# Main.net
KiCad netlist of a schematic drawn in Altium Designer
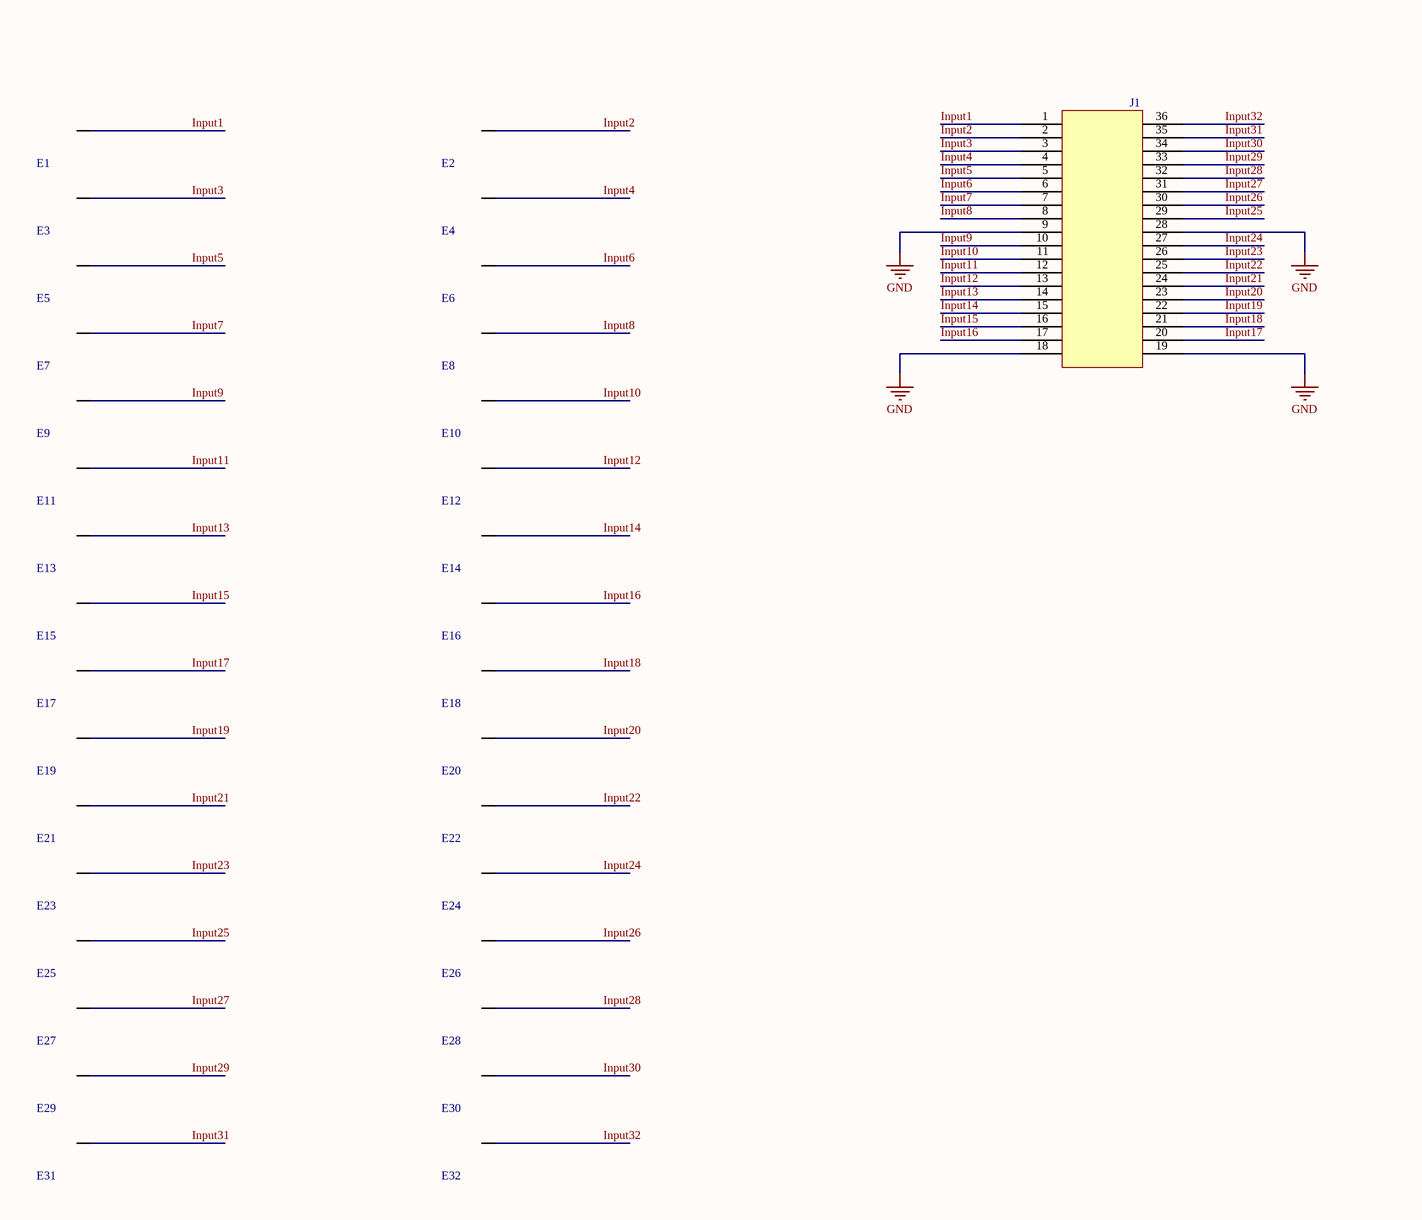
[diagram p0: Main.SchDoc, left]
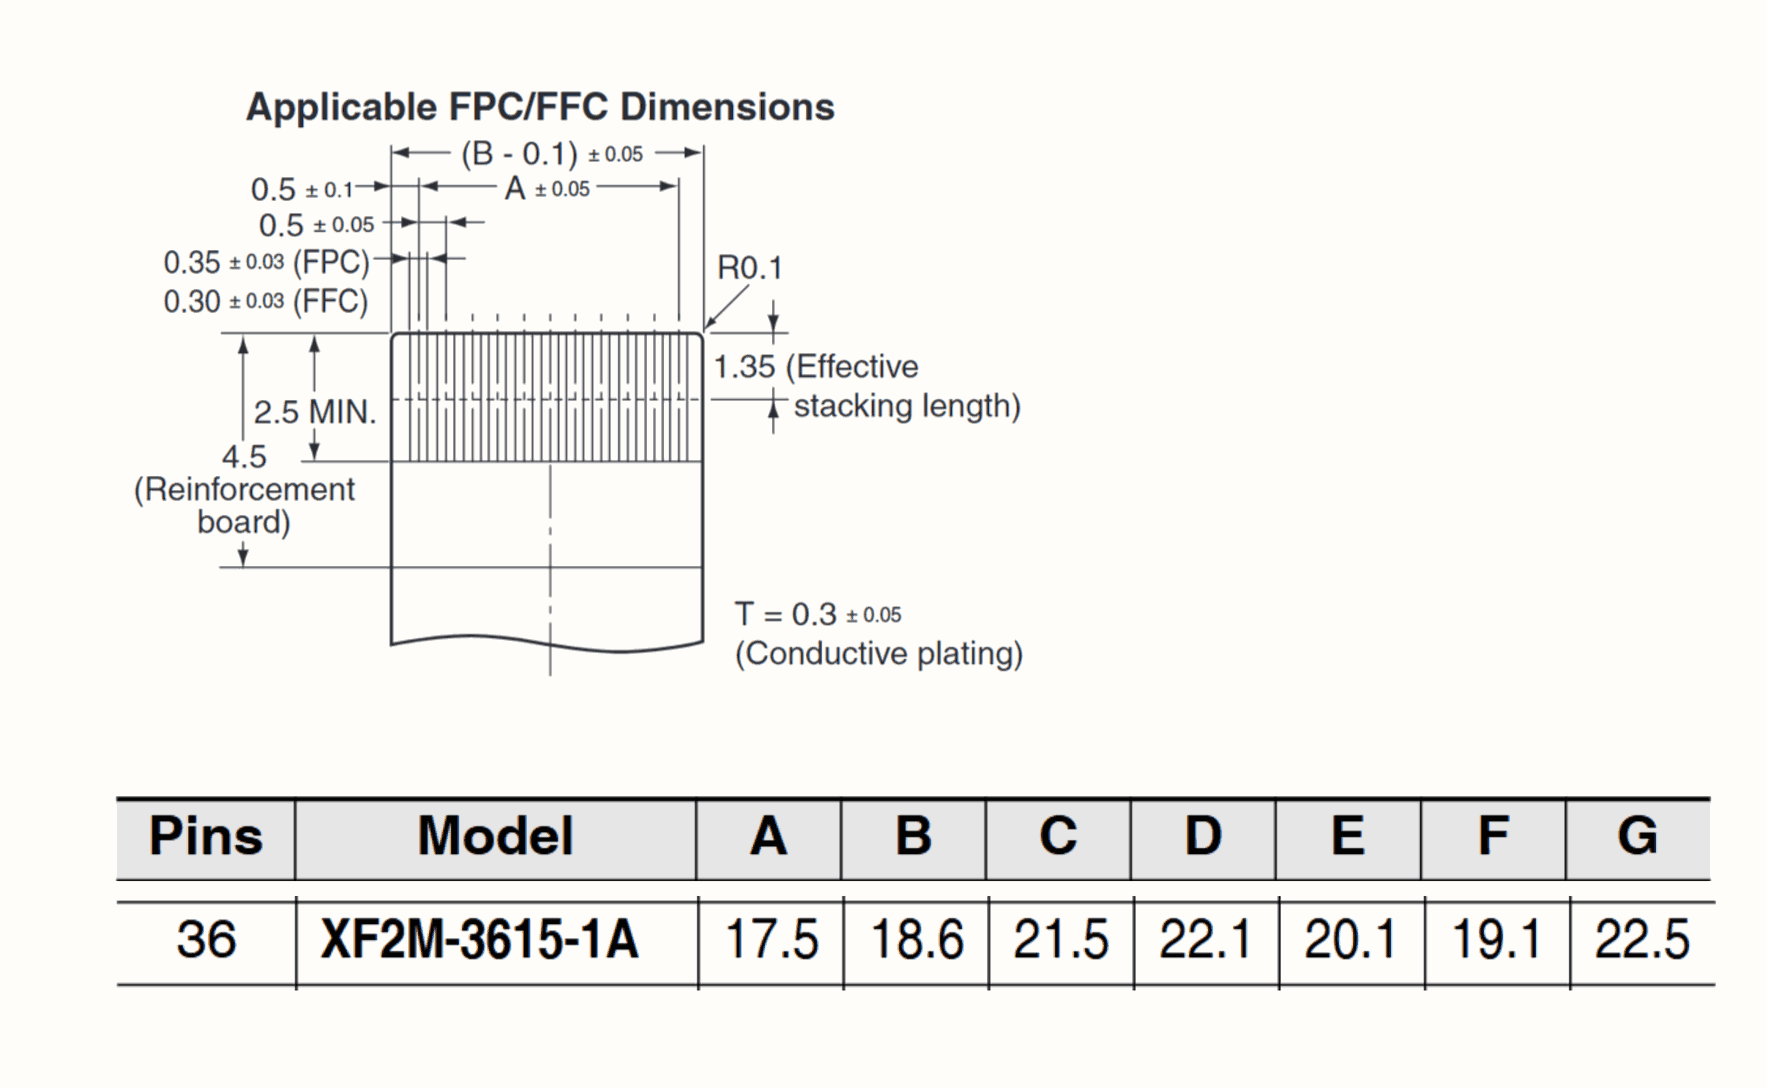
[diagram p1: Main.SchDoc, right]

(export (version "E")
  (design (tool "Eeschema 10.0.6"))
  (components
    (comp (ref "E1")
      (value "2.5 mm")
      (footprint "PCBComponent_1")
      (description "Microneedle electrode - 2.5 mm diameter")
      (libsource (lib "Microneedle_Lib") (part "SENSE_UNEEDLE"))
    )
    (comp (ref "E2")
      (value "2.5 mm")
      (footprint "PCBComponent_1")
      (description "Microneedle electrode - 2.5 mm diameter")
      (libsource (lib "Microneedle_Lib") (part "SENSE_UNEEDLE"))
    )
    (comp (ref "E3")
      (value "2.5 mm")
      (footprint "PCBComponent_1")
      (description "Microneedle electrode - 2.5 mm diameter")
      (libsource (lib "Microneedle_Lib") (part "SENSE_UNEEDLE"))
    )
    (comp (ref "E4")
      (value "2.5 mm")
      (footprint "PCBComponent_1")
      (description "Microneedle electrode - 2.5 mm diameter")
      (libsource (lib "Microneedle_Lib") (part "SENSE_UNEEDLE"))
    )
    (comp (ref "E5")
      (value "2.5 mm")
      (footprint "PCBComponent_1")
      (description "Microneedle electrode - 2.5 mm diameter")
      (libsource (lib "Microneedle_Lib") (part "SENSE_UNEEDLE"))
    )
    (comp (ref "E6")
      (value "2.5 mm")
      (footprint "PCBComponent_1")
      (description "Microneedle electrode - 2.5 mm diameter")
      (libsource (lib "Microneedle_Lib") (part "SENSE_UNEEDLE"))
    )
    (comp (ref "E7")
      (value "2.5 mm")
      (footprint "PCBComponent_1")
      (description "Microneedle electrode - 2.5 mm diameter")
      (libsource (lib "Microneedle_Lib") (part "SENSE_UNEEDLE"))
    )
    (comp (ref "E8")
      (value "2.5 mm")
      (footprint "PCBComponent_1")
      (description "Microneedle electrode - 2.5 mm diameter")
      (libsource (lib "Microneedle_Lib") (part "SENSE_UNEEDLE"))
    )
    (comp (ref "E9")
      (value "2.5 mm")
      (footprint "PCBComponent_1")
      (description "Microneedle electrode - 2.5 mm diameter")
      (libsource (lib "Microneedle_Lib") (part "SENSE_UNEEDLE"))
    )
    (comp (ref "E10")
      (value "2.5 mm")
      (footprint "PCBComponent_1")
      (description "Microneedle electrode - 2.5 mm diameter")
      (libsource (lib "Microneedle_Lib") (part "SENSE_UNEEDLE"))
    )
    (comp (ref "E11")
      (value "2.5 mm")
      (footprint "PCBComponent_1")
      (description "Microneedle electrode - 2.5 mm diameter")
      (libsource (lib "Microneedle_Lib") (part "SENSE_UNEEDLE"))
    )
    (comp (ref "E12")
      (value "2.5 mm")
      (footprint "PCBComponent_1")
      (description "Microneedle electrode - 2.5 mm diameter")
      (libsource (lib "Microneedle_Lib") (part "SENSE_UNEEDLE"))
    )
    (comp (ref "E13")
      (value "2.5 mm")
      (footprint "PCBComponent_1")
      (description "Microneedle electrode - 2.5 mm diameter")
      (libsource (lib "Microneedle_Lib") (part "SENSE_UNEEDLE"))
    )
    (comp (ref "E14")
      (value "2.5 mm")
      (footprint "PCBComponent_1")
      (description "Microneedle electrode - 2.5 mm diameter")
      (libsource (lib "Microneedle_Lib") (part "SENSE_UNEEDLE"))
    )
    (comp (ref "E15")
      (value "2.5 mm")
      (footprint "PCBComponent_1")
      (description "Microneedle electrode - 2.5 mm diameter")
      (libsource (lib "Microneedle_Lib") (part "SENSE_UNEEDLE"))
    )
    (comp (ref "E16")
      (value "2.5 mm")
      (footprint "PCBComponent_1")
      (description "Microneedle electrode - 2.5 mm diameter")
      (libsource (lib "Microneedle_Lib") (part "SENSE_UNEEDLE"))
    )
    (comp (ref "E17")
      (value "2.5 mm")
      (footprint "PCBComponent_1")
      (description "Microneedle electrode - 2.5 mm diameter")
      (libsource (lib "Microneedle_Lib") (part "SENSE_UNEEDLE"))
    )
    (comp (ref "E18")
      (value "2.5 mm")
      (footprint "PCBComponent_1")
      (description "Microneedle electrode - 2.5 mm diameter")
      (libsource (lib "Microneedle_Lib") (part "SENSE_UNEEDLE"))
    )
    (comp (ref "E19")
      (value "2.5 mm")
      (footprint "PCBComponent_1")
      (description "Microneedle electrode - 2.5 mm diameter")
      (libsource (lib "Microneedle_Lib") (part "SENSE_UNEEDLE"))
    )
    (comp (ref "E20")
      (value "2.5 mm")
      (footprint "PCBComponent_1")
      (description "Microneedle electrode - 2.5 mm diameter")
      (libsource (lib "Microneedle_Lib") (part "SENSE_UNEEDLE"))
    )
    (comp (ref "E21")
      (value "2.5 mm")
      (footprint "PCBComponent_1")
      (description "Microneedle electrode - 2.5 mm diameter")
      (libsource (lib "Microneedle_Lib") (part "SENSE_UNEEDLE"))
    )
    (comp (ref "E22")
      (value "2.5 mm")
      (footprint "PCBComponent_1")
      (description "Microneedle electrode - 2.5 mm diameter")
      (libsource (lib "Microneedle_Lib") (part "SENSE_UNEEDLE"))
    )
    (comp (ref "E23")
      (value "2.5 mm")
      (footprint "PCBComponent_1")
      (description "Microneedle electrode - 2.5 mm diameter")
      (libsource (lib "Microneedle_Lib") (part "SENSE_UNEEDLE"))
    )
    (comp (ref "E24")
      (value "2.5 mm")
      (footprint "PCBComponent_1")
      (description "Microneedle electrode - 2.5 mm diameter")
      (libsource (lib "Microneedle_Lib") (part "SENSE_UNEEDLE"))
    )
    (comp (ref "E25")
      (value "2.5 mm")
      (footprint "PCBComponent_1")
      (description "Microneedle electrode - 2.5 mm diameter")
      (libsource (lib "Microneedle_Lib") (part "SENSE_UNEEDLE"))
    )
    (comp (ref "E26")
      (value "2.5 mm")
      (footprint "PCBComponent_1")
      (description "Microneedle electrode - 2.5 mm diameter")
      (libsource (lib "Microneedle_Lib") (part "SENSE_UNEEDLE"))
    )
    (comp (ref "E27")
      (value "2.5 mm")
      (footprint "PCBComponent_1")
      (description "Microneedle electrode - 2.5 mm diameter")
      (libsource (lib "Microneedle_Lib") (part "SENSE_UNEEDLE"))
    )
    (comp (ref "E28")
      (value "2.5 mm")
      (footprint "PCBComponent_1")
      (description "Microneedle electrode - 2.5 mm diameter")
      (libsource (lib "Microneedle_Lib") (part "SENSE_UNEEDLE"))
    )
    (comp (ref "E29")
      (value "2.5 mm")
      (footprint "PCBComponent_1")
      (description "Microneedle electrode - 2.5 mm diameter")
      (libsource (lib "Microneedle_Lib") (part "SENSE_UNEEDLE"))
    )
    (comp (ref "E30")
      (value "2.5 mm")
      (footprint "PCBComponent_1")
      (description "Microneedle electrode - 2.5 mm diameter")
      (libsource (lib "Microneedle_Lib") (part "SENSE_UNEEDLE"))
    )
    (comp (ref "E31")
      (value "2.5 mm")
      (footprint "PCBComponent_1")
      (description "Microneedle electrode - 2.5 mm diameter")
      (libsource (lib "Microneedle_Lib") (part "SENSE_UNEEDLE"))
    )
    (comp (ref "E32")
      (value "2.5 mm")
      (footprint "PCBComponent_1")
      (description "Microneedle electrode - 2.5 mm diameter")
      (libsource (lib "Microneedle_Lib") (part "SENSE_UNEEDLE"))
    )
    (comp (ref "J1")
      (value "XF2M-3615-1A")
      (footprint "CONN_FPC_2X18_0MM5")
      (description "FPC Connector - FPC Side. 0.5 mm pitch\r\nCompatible with XF2M-3615-1A")
      (libsource (lib "Microneedle_Lib") (part "CONN_FPC_2X18_0MM5"))
    )
  )
  (nets
    (net (code "1") (name "/Input1") (class "Default")
      (node (ref "E1") (pin "1") (pinfunction "E_1") (pintype "passive"))
      (node (ref "J1") (pin "1") (pinfunction "1_1") (pintype "passive"))
    )
    (net (code "2") (name "/Input2") (class "Default")
      (node (ref "E2") (pin "1") (pinfunction "E_1") (pintype "passive"))
      (node (ref "J1") (pin "2") (pinfunction "2_2") (pintype "passive"))
    )
    (net (code "3") (name "/Input3") (class "Default")
      (node (ref "E3") (pin "1") (pinfunction "E_1") (pintype "passive"))
      (node (ref "J1") (pin "3") (pinfunction "3_3") (pintype "passive"))
    )
    (net (code "4") (name "/Input4") (class "Default")
      (node (ref "E4") (pin "1") (pinfunction "E_1") (pintype "passive"))
      (node (ref "J1") (pin "4") (pinfunction "4_4") (pintype "passive"))
    )
    (net (code "5") (name "/Input5") (class "Default")
      (node (ref "E5") (pin "1") (pinfunction "E_1") (pintype "passive"))
      (node (ref "J1") (pin "5") (pinfunction "5_5") (pintype "passive"))
    )
    (net (code "6") (name "/Input6") (class "Default")
      (node (ref "E6") (pin "1") (pinfunction "E_1") (pintype "passive"))
      (node (ref "J1") (pin "6") (pinfunction "6_6") (pintype "passive"))
    )
    (net (code "7") (name "/Input7") (class "Default")
      (node (ref "E7") (pin "1") (pinfunction "E_1") (pintype "passive"))
      (node (ref "J1") (pin "7") (pinfunction "7_7") (pintype "passive"))
    )
    (net (code "8") (name "/Input8") (class "Default")
      (node (ref "E8") (pin "1") (pinfunction "E_1") (pintype "passive"))
      (node (ref "J1") (pin "8") (pinfunction "8_8") (pintype "passive"))
    )
    (net (code "9") (name "/Input9") (class "Default")
      (node (ref "E9") (pin "1") (pinfunction "E_1") (pintype "passive"))
      (node (ref "J1") (pin "10") (pinfunction "10_10") (pintype "passive"))
    )
    (net (code "10") (name "/Input10") (class "Default")
      (node (ref "E10") (pin "1") (pinfunction "E_1") (pintype "passive"))
      (node (ref "J1") (pin "11") (pinfunction "11_11") (pintype "passive"))
    )
    (net (code "11") (name "/Input11") (class "Default")
      (node (ref "E11") (pin "1") (pinfunction "E_1") (pintype "passive"))
      (node (ref "J1") (pin "12") (pinfunction "12_12") (pintype "passive"))
    )
    (net (code "12") (name "/Input12") (class "Default")
      (node (ref "E12") (pin "1") (pinfunction "E_1") (pintype "passive"))
      (node (ref "J1") (pin "13") (pinfunction "13_13") (pintype "passive"))
    )
    (net (code "13") (name "/Input13") (class "Default")
      (node (ref "E13") (pin "1") (pinfunction "E_1") (pintype "passive"))
      (node (ref "J1") (pin "14") (pinfunction "14_14") (pintype "passive"))
    )
    (net (code "14") (name "/Input14") (class "Default")
      (node (ref "E14") (pin "1") (pinfunction "E_1") (pintype "passive"))
      (node (ref "J1") (pin "15") (pinfunction "15_15") (pintype "passive"))
    )
    (net (code "15") (name "/Input15") (class "Default")
      (node (ref "E15") (pin "1") (pinfunction "E_1") (pintype "passive"))
      (node (ref "J1") (pin "16") (pinfunction "16_16") (pintype "passive"))
    )
    (net (code "16") (name "/Input16") (class "Default")
      (node (ref "E16") (pin "1") (pinfunction "E_1") (pintype "passive"))
      (node (ref "J1") (pin "17") (pinfunction "17_17") (pintype "passive"))
    )
    (net (code "17") (name "/Input17") (class "Default")
      (node (ref "E17") (pin "1") (pinfunction "E_1") (pintype "passive"))
      (node (ref "J1") (pin "20") (pinfunction "20_20") (pintype "passive"))
    )
    (net (code "18") (name "/Input18") (class "Default")
      (node (ref "E18") (pin "1") (pinfunction "E_1") (pintype "passive"))
      (node (ref "J1") (pin "21") (pinfunction "21_21") (pintype "passive"))
    )
    (net (code "19") (name "/Input19") (class "Default")
      (node (ref "E19") (pin "1") (pinfunction "E_1") (pintype "passive"))
      (node (ref "J1") (pin "22") (pinfunction "22_22") (pintype "passive"))
    )
    (net (code "20") (name "/Input20") (class "Default")
      (node (ref "E20") (pin "1") (pinfunction "E_1") (pintype "passive"))
      (node (ref "J1") (pin "23") (pinfunction "23_23") (pintype "passive"))
    )
    (net (code "21") (name "/Input21") (class "Default")
      (node (ref "E21") (pin "1") (pinfunction "E_1") (pintype "passive"))
      (node (ref "J1") (pin "24") (pinfunction "24_24") (pintype "passive"))
    )
    (net (code "22") (name "/Input22") (class "Default")
      (node (ref "E22") (pin "1") (pinfunction "E_1") (pintype "passive"))
      (node (ref "J1") (pin "25") (pinfunction "25_25") (pintype "passive"))
    )
    (net (code "23") (name "/Input23") (class "Default")
      (node (ref "E23") (pin "1") (pinfunction "E_1") (pintype "passive"))
      (node (ref "J1") (pin "26") (pinfunction "26_26") (pintype "passive"))
    )
    (net (code "24") (name "/Input24") (class "Default")
      (node (ref "E24") (pin "1") (pinfunction "E_1") (pintype "passive"))
      (node (ref "J1") (pin "27") (pinfunction "27_27") (pintype "passive"))
    )
    (net (code "25") (name "/Input25") (class "Default")
      (node (ref "E25") (pin "1") (pinfunction "E_1") (pintype "passive"))
      (node (ref "J1") (pin "29") (pinfunction "29_29") (pintype "passive"))
    )
    (net (code "26") (name "/Input26") (class "Default")
      (node (ref "E26") (pin "1") (pinfunction "E_1") (pintype "passive"))
      (node (ref "J1") (pin "30") (pinfunction "30_30") (pintype "passive"))
    )
    (net (code "27") (name "/Input27") (class "Default")
      (node (ref "E27") (pin "1") (pinfunction "E_1") (pintype "passive"))
      (node (ref "J1") (pin "31") (pinfunction "31_31") (pintype "passive"))
    )
    (net (code "28") (name "/Input28") (class "Default")
      (node (ref "E28") (pin "1") (pinfunction "E_1") (pintype "passive"))
      (node (ref "J1") (pin "32") (pinfunction "32_32") (pintype "passive"))
    )
    (net (code "29") (name "/Input29") (class "Default")
      (node (ref "E29") (pin "1") (pinfunction "E_1") (pintype "passive"))
      (node (ref "J1") (pin "33") (pinfunction "33_33") (pintype "passive"))
    )
    (net (code "30") (name "/Input30") (class "Default")
      (node (ref "E30") (pin "1") (pinfunction "E_1") (pintype "passive"))
      (node (ref "J1") (pin "34") (pinfunction "34_34") (pintype "passive"))
    )
    (net (code "31") (name "/Input31") (class "Default")
      (node (ref "E31") (pin "1") (pinfunction "E_1") (pintype "passive"))
      (node (ref "J1") (pin "35") (pinfunction "35_35") (pintype "passive"))
    )
    (net (code "32") (name "/Input32") (class "Default")
      (node (ref "E32") (pin "1") (pinfunction "E_1") (pintype "passive"))
      (node (ref "J1") (pin "36") (pinfunction "36_36") (pintype "passive"))
    )
    (net (code "33") (name "GND") (class "Default")
      (node (ref "J1") (pin "18") (pinfunction "18_18") (pintype "passive"))
      (node (ref "J1") (pin "19") (pinfunction "19_19") (pintype "passive"))
      (node (ref "J1") (pin "28") (pinfunction "28_28") (pintype "passive"))
      (node (ref "J1") (pin "9") (pinfunction "9_9") (pintype "passive"))
    )
  )
)
